# 05_-_BMS.net
KiCad netlist of a schematic drawn in Altium Designer
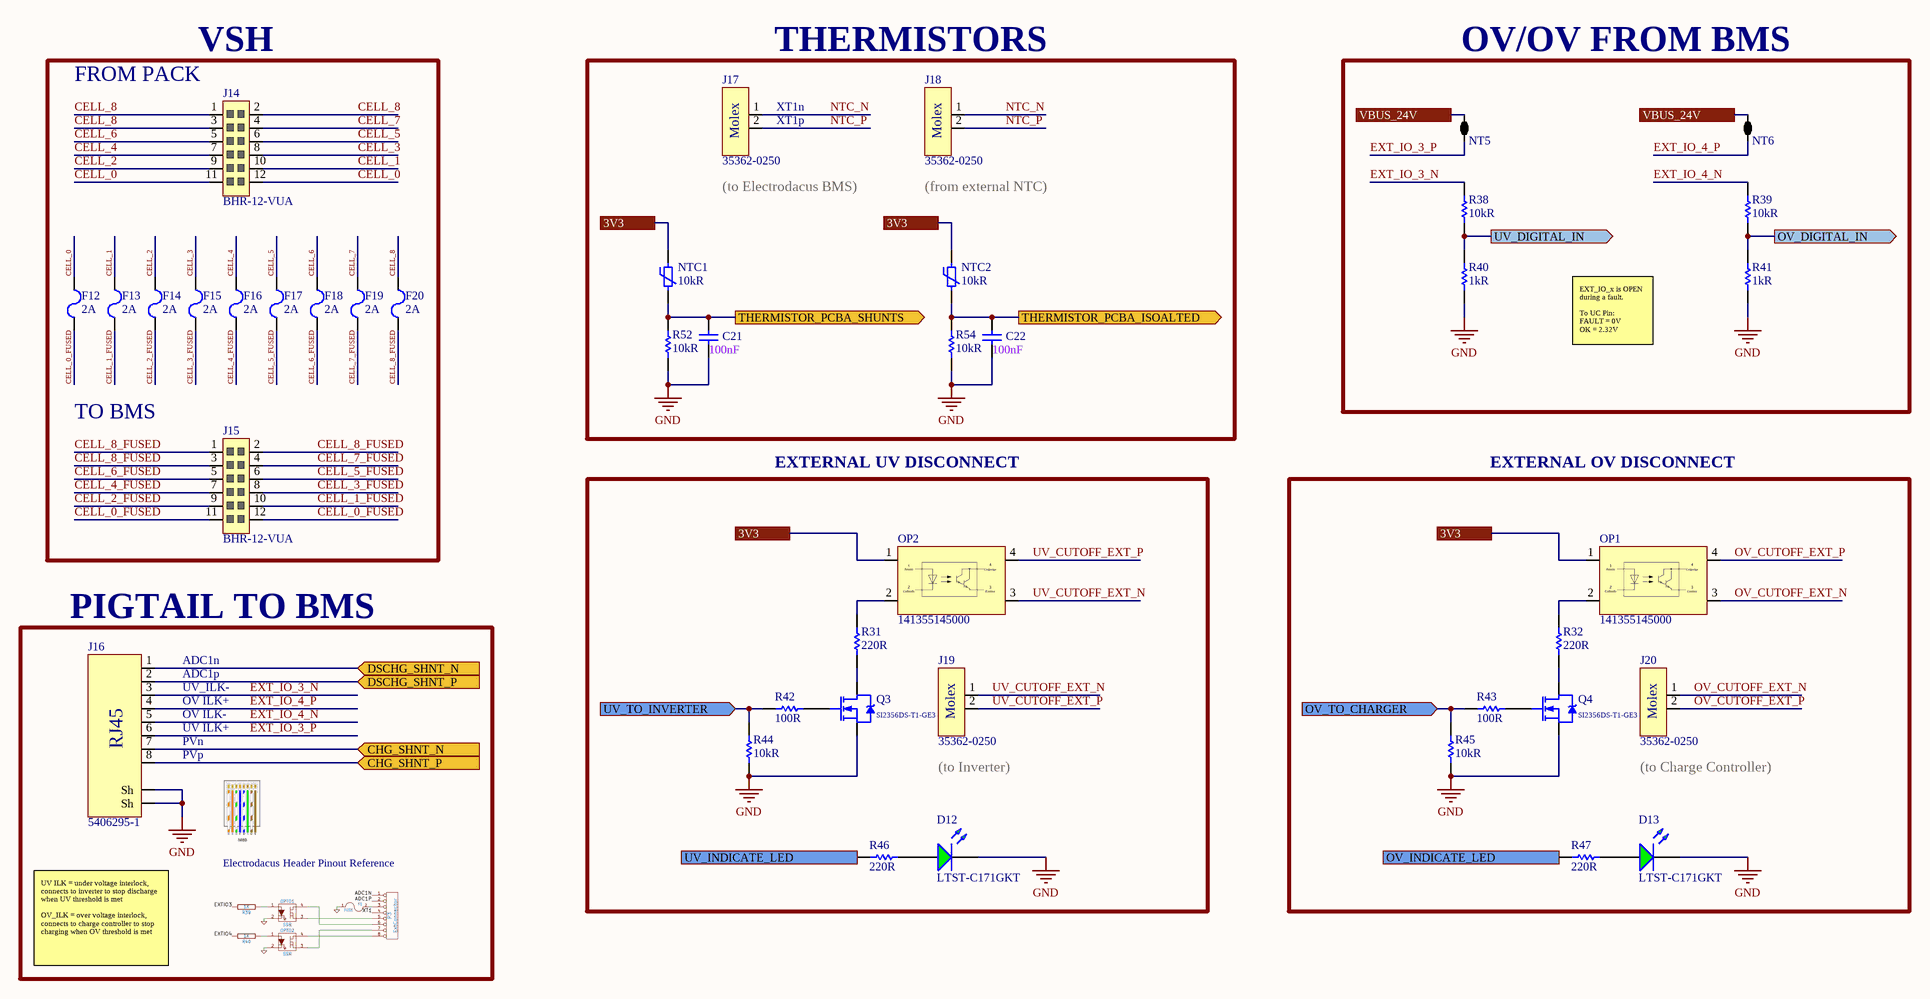
[diagram p0: [05] - BMS.SchDoc]

(export (version "E")
  (design (tool "Eeschema 10.0.6"))
  (components
    (comp (ref "C21")
      (value "100nF")
      (footprint "INCH 0603 - METRIC 1608 - H090")
      (description "CAP CER 0.1UF 25V X7R 0603")
      (fields
        (field (name "MANUFACTURER") "TDK")
        (field (name "MANUFACTURER PART NUMBER") "CGA3E2X7R1E104K080AA")
      )
      (libsource (lib "Capacitors") (part "CGA3E2X7R1E104K080AA"))
    )
    (comp (ref "C22")
      (value "100nF")
      (footprint "INCH 0603 - METRIC 1608 - H090")
      (description "CAP CER 0.1UF 25V X7R 0603")
      (fields
        (field (name "MANUFACTURER") "TDK")
        (field (name "MANUFACTURER PART NUMBER") "CGA3E2X7R1E104K080AA")
      )
      (libsource (lib "Capacitors") (part "CGA3E2X7R1E104K080AA"))
    )
    (comp (ref "D12")
      (value "LTST-C171GKT")
      (footprint "LED - 0805 - GREEN")
      (fields (field (name "MANUFACTURER") "Vishay Lite-On"))
      (libsource (lib "LEDs") (part "LTST-C171GKT"))
    )
    (comp (ref "D13")
      (value "LTST-C171GKT")
      (footprint "LED - 0805 - GREEN")
      (fields (field (name "MANUFACTURER") "Vishay Lite-On"))
      (libsource (lib "LEDs") (part "LTST-C171GKT"))
    )
    (comp (ref "F12")
      (value "MFU0805FF02000P500")
      (footprint "FUSC0805x45")
      (description "FUSE 2A 32V SMT 0805 THIN")
      (fields (field (name "CURRENT RATING") "2A"))
      (libsource (lib "Fuses") (part "MFU0805FF02000P500"))
    )
    (comp (ref "F13")
      (value "MFU0805FF02000P500")
      (footprint "FUSC0805x45")
      (description "FUSE 2A 32V SMT 0805 THIN")
      (fields (field (name "CURRENT RATING") "2A"))
      (libsource (lib "Fuses") (part "MFU0805FF02000P500"))
    )
    (comp (ref "F14")
      (value "MFU0805FF02000P500")
      (footprint "FUSC0805x45")
      (description "FUSE 2A 32V SMT 0805 THIN")
      (fields (field (name "CURRENT RATING") "2A"))
      (libsource (lib "Fuses") (part "MFU0805FF02000P500"))
    )
    (comp (ref "F15")
      (value "MFU0805FF02000P500")
      (footprint "FUSC0805x45")
      (description "FUSE 2A 32V SMT 0805 THIN")
      (fields (field (name "CURRENT RATING") "2A"))
      (libsource (lib "Fuses") (part "MFU0805FF02000P500"))
    )
    (comp (ref "F16")
      (value "MFU0805FF02000P500")
      (footprint "FUSC0805x45")
      (description "FUSE 2A 32V SMT 0805 THIN")
      (fields (field (name "CURRENT RATING") "2A"))
      (libsource (lib "Fuses") (part "MFU0805FF02000P500"))
    )
    (comp (ref "F17")
      (value "MFU0805FF02000P500")
      (footprint "FUSC0805x45")
      (description "FUSE 2A 32V SMT 0805 THIN")
      (fields (field (name "CURRENT RATING") "2A"))
      (libsource (lib "Fuses") (part "MFU0805FF02000P500"))
    )
    (comp (ref "F18")
      (value "MFU0805FF02000P500")
      (footprint "FUSC0805x45")
      (description "FUSE 2A 32V SMT 0805 THIN")
      (fields (field (name "CURRENT RATING") "2A"))
      (libsource (lib "Fuses") (part "MFU0805FF02000P500"))
    )
    (comp (ref "F19")
      (value "MFU0805FF02000P500")
      (footprint "FUSC0805x45")
      (description "FUSE 2A 32V SMT 0805 THIN")
      (fields (field (name "CURRENT RATING") "2A"))
      (libsource (lib "Fuses") (part "MFU0805FF02000P500"))
    )
    (comp (ref "F20")
      (value "MFU0805FF02000P500")
      (footprint "FUSC0805x45")
      (description "FUSE 2A 32V SMT 0805 THIN")
      (fields (field (name "CURRENT RATING") "2A"))
      (libsource (lib "Fuses") (part "MFU0805FF02000P500"))
    )
    (comp (ref "J14")
      (value "BHR-12-VUA")
      (footprint "SHDRV12W64P254_6X2_2284X880H880")
      (description "CONN HEADER VERT 12POS 2.54MM")
      (fields (field (name "MANUFACTURER") "Adam Tech"))
      (libsource (lib "Connectors - Headers") (part "BHR-12-VUA"))
    )
    (comp (ref "J15")
      (value "BHR-12-VUA")
      (footprint "SHDRV12W64P254_6X2_2284X880H880")
      (description "CONN HEADER VERT 12POS 2.54MM")
      (fields (field (name "MANUFACTURER") "Adam Tech"))
      (libsource (lib "Connectors - Headers") (part "BHR-12-VUA"))
    )
    (comp (ref "J16")
      (value "5406295-1")
      (footprint "TE_5406295-1")
      (description "Conn RJ-45 F 8 POS RA Thru-Hole")
      (fields (field (name "MANUFACTURER") "TE Connectivity"))
      (libsource (lib "Connectors") (part "5406295-1"))
    )
    (comp (ref "J17")
      (value "35362-0250")
      (footprint "MOLEX_35362")
      (description "Conn Shrouded Header HDR 2 POS 2mm Solder ST Thru-Hole Bag")
      (fields (field (name "MANUFACTURER") "Molex"))
      (libsource (lib "Connectors") (part "35362-0250"))
    )
    (comp (ref "J18")
      (value "35362-0250")
      (footprint "MOLEX_35362")
      (description "Conn Shrouded Header HDR 2 POS 2mm Solder ST Thru-Hole Bag")
      (fields (field (name "MANUFACTURER") "Molex"))
      (libsource (lib "Connectors") (part "35362-0250"))
    )
    (comp (ref "J19")
      (value "35362-0250")
      (footprint "MOLEX_35362")
      (description "Conn Shrouded Header HDR 2 POS 2mm Solder ST Thru-Hole Bag")
      (fields (field (name "MANUFACTURER") "Molex"))
      (libsource (lib "Connectors") (part "35362-0250"))
    )
    (comp (ref "J20")
      (value "35362-0250")
      (footprint "MOLEX_35362")
      (description "Conn Shrouded Header HDR 2 POS 2mm Solder ST Thru-Hole Bag")
      (fields (field (name "MANUFACTURER") "Molex"))
      (libsource (lib "Connectors") (part "35362-0250"))
    )
    (comp (ref "NT5")
      (value "2 way net tie junction")
      (footprint "2way_LP")
      (libsource (lib "Net Ties") (part "2way"))
    )
    (comp (ref "NT6")
      (value "2 way net tie junction")
      (footprint "2way_LP")
      (libsource (lib "Net Ties") (part "2way"))
    )
    (comp (ref "NTC1")
      (value "10kR")
      (footprint "INCH 0603 - METRIC 1608 - H055N")
      (description "Thermistor NTC 10K Ohm 3% 2-Pin 0603 Surface Mount Solder Pad 3934K T/R")
      (fields
        (field (name "MANUFACTURER") "Murata")
        (field (name "MANUFACTURER PART NUMBER") "NCP18XV103E03RB")
      )
      (libsource (lib "Thermistors") (part "NCP18XV103E03RB"))
    )
    (comp (ref "NTC2")
      (value "10kR")
      (footprint "INCH 0603 - METRIC 1608 - H055N")
      (description "Thermistor NTC 10K Ohm 3% 2-Pin 0603 Surface Mount Solder Pad 3934K T/R")
      (fields
        (field (name "MANUFACTURER") "Murata")
        (field (name "MANUFACTURER PART NUMBER") "NCP18XV103E03RB")
      )
      (libsource (lib "Thermistors") (part "NCP18XV103E03RB"))
    )
    (comp (ref "OP1")
      (value "141355145000")
      (footprint "SOT23-4P127_700X210L50X40N")
      (description "Optocoupler, Transistor, 3.75Kv, Sop Rohs Compliant: Yes")
      (fields (field (name "MANUFACTURER") "Wurth Electronics"))
      (libsource (lib "ICs - Drivers") (part "141355145000"))
    )
    (comp (ref "OP2")
      (value "141355145000")
      (footprint "SOT23-4P127_700X210L50X40N")
      (description "Optocoupler, Transistor, 3.75Kv, Sop Rohs Compliant: Yes")
      (fields (field (name "MANUFACTURER") "Wurth Electronics"))
      (libsource (lib "ICs - Drivers") (part "141355145000"))
    )
    (comp (ref "Q3")
      (value "SI2356DS-T1-GE3")
      (footprint "SOT23-3P95_237X112L50X42N")
      (description "Si2356DS Series 40 V 3.2 A 51 mOhm Surface Mount N-Channel Mosfet - SOT-23-3")
      (fields (field (name "MANUFACTURER") "Vishay Siliconix"))
      (libsource (lib "Transistors - FET") (part "SI2356DS-T1-GE3"))
    )
    (comp (ref "Q4")
      (value "SI2356DS-T1-GE3")
      (footprint "SOT23-3P95_237X112L50X42N")
      (description "Si2356DS Series 40 V 3.2 A 51 mOhm Surface Mount N-Channel Mosfet - SOT-23-3")
      (fields (field (name "MANUFACTURER") "Vishay Siliconix"))
      (libsource (lib "Transistors - FET") (part "SI2356DS-T1-GE3"))
    )
    (comp (ref "R31")
      (value "220R")
      (footprint "INCH 0603 - METRIC 1608 - H055")
      (description "RES SMD 220 OHM 1% 1/10W 0603")
      (fields
        (field (name "MANUFACTURER") "Yageo")
        (field (name "MANUFACTURER PART NUMBER") "RC0603FR-07220RL")
      )
      (libsource (lib "Resistors") (part "RC0603FR-07220RL"))
    )
    (comp (ref "R32")
      (value "220R")
      (footprint "INCH 0603 - METRIC 1608 - H055")
      (description "RES SMD 220 OHM 1% 1/10W 0603")
      (fields
        (field (name "MANUFACTURER") "Yageo")
        (field (name "MANUFACTURER PART NUMBER") "RC0603FR-07220RL")
      )
      (libsource (lib "Resistors") (part "RC0603FR-07220RL"))
    )
    (comp (ref "R38")
      (value "10kR")
      (footprint "INCH 0603 - METRIC 1508 - H050")
      (description "RES SMD 10K OHM 0.5% 1/16W 0603")
      (fields
        (field (name "MANUFACTURER") "Susumu")
        (field (name "MANUFACTURER PART NUMBER") "RR0816P-103-D")
      )
      (libsource (lib "Resistors") (part "RR0816P-103-D"))
    )
    (comp (ref "R39")
      (value "10kR")
      (footprint "INCH 0603 - METRIC 1508 - H050")
      (description "RES SMD 10K OHM 0.5% 1/16W 0603")
      (fields
        (field (name "MANUFACTURER") "Susumu")
        (field (name "MANUFACTURER PART NUMBER") "RR0816P-103-D")
      )
      (libsource (lib "Resistors") (part "RR0816P-103-D"))
    )
    (comp (ref "R40")
      (value "1kR")
      (footprint "INCH 0603 - METRIC 1508 - H050")
      (description "RES SMD 1K OHM 1% 1/10W 0603")
      (fields
        (field (name "MANUFACTURER") "Vishay Dale")
        (field (name "MANUFACTURER PART NUMBER") "CRCW06031K00FKEA")
      )
      (libsource (lib "Resistors") (part "CRCW06031K00FKEA"))
    )
    (comp (ref "R41")
      (value "1kR")
      (footprint "INCH 0603 - METRIC 1508 - H050")
      (description "RES SMD 1K OHM 1% 1/10W 0603")
      (fields
        (field (name "MANUFACTURER") "Vishay Dale")
        (field (name "MANUFACTURER PART NUMBER") "CRCW06031K00FKEA")
      )
      (libsource (lib "Resistors") (part "CRCW06031K00FKEA"))
    )
    (comp (ref "R42")
      (value "100R")
      (footprint "INCH 0603 - METRIC 1608 - H055")
      (description "RES SMD 100 OHM 0.1% 1/16W 0603")
      (fields
        (field (name "MANUFACTURER") "TE Connectivity Neohm")
        (field (name "MANUFACTURER PART NUMBER") "CPF0603B100RE1")
      )
      (libsource (lib "Resistors") (part "CPF0603B100RE1"))
    )
    (comp (ref "R43")
      (value "100R")
      (footprint "INCH 0603 - METRIC 1608 - H055")
      (description "RES SMD 100 OHM 0.1% 1/16W 0603")
      (fields
        (field (name "MANUFACTURER") "TE Connectivity Neohm")
        (field (name "MANUFACTURER PART NUMBER") "CPF0603B100RE1")
      )
      (libsource (lib "Resistors") (part "CPF0603B100RE1"))
    )
    (comp (ref "R44")
      (value "10kR")
      (footprint "INCH 0603 - METRIC 1508 - H050")
      (description "RES SMD 10K OHM 0.5% 1/16W 0603")
      (fields
        (field (name "MANUFACTURER") "Susumu")
        (field (name "MANUFACTURER PART NUMBER") "RR0816P-103-D")
      )
      (libsource (lib "Resistors") (part "RR0816P-103-D"))
    )
    (comp (ref "R45")
      (value "10kR")
      (footprint "INCH 0603 - METRIC 1508 - H050")
      (description "RES SMD 10K OHM 0.5% 1/16W 0603")
      (fields
        (field (name "MANUFACTURER") "Susumu")
        (field (name "MANUFACTURER PART NUMBER") "RR0816P-103-D")
      )
      (libsource (lib "Resistors") (part "RR0816P-103-D"))
    )
    (comp (ref "R46")
      (value "220R")
      (footprint "INCH 0603 - METRIC 1608 - H055")
      (description "RES SMD 220 OHM 1% 1/10W 0603")
      (fields
        (field (name "MANUFACTURER") "Yageo")
        (field (name "MANUFACTURER PART NUMBER") "RC0603FR-07220RL")
      )
      (libsource (lib "Resistors") (part "RC0603FR-07220RL"))
    )
    (comp (ref "R47")
      (value "220R")
      (footprint "INCH 0603 - METRIC 1608 - H055")
      (description "RES SMD 220 OHM 1% 1/10W 0603")
      (fields
        (field (name "MANUFACTURER") "Yageo")
        (field (name "MANUFACTURER PART NUMBER") "RC0603FR-07220RL")
      )
      (libsource (lib "Resistors") (part "RC0603FR-07220RL"))
    )
    (comp (ref "R52")
      (value "10kR")
      (footprint "INCH 0603 - METRIC 1508 - H050")
      (description "RES SMD 10K OHM 0.5% 1/16W 0603")
      (fields
        (field (name "MANUFACTURER") "Susumu")
        (field (name "MANUFACTURER PART NUMBER") "RR0816P-103-D")
      )
      (libsource (lib "Resistors") (part "RR0816P-103-D"))
    )
    (comp (ref "R54")
      (value "10kR")
      (footprint "INCH 0603 - METRIC 1508 - H050")
      (description "RES SMD 10K OHM 0.5% 1/16W 0603")
      (fields
        (field (name "MANUFACTURER") "Susumu")
        (field (name "MANUFACTURER PART NUMBER") "RR0816P-103-D")
      )
      (libsource (lib "Resistors") (part "RR0816P-103-D"))
    )
  )
  (nets
    (net (code "1") (name "/3V3") (class "Default")
      (node (ref "NTC1") (pin "2") (pintype "passive"))
      (node (ref "NTC2") (pin "2") (pintype "passive"))
      (node (ref "OP1") (pin "1") (pinfunction "A_1") (pintype "passive"))
      (node (ref "OP2") (pin "1") (pinfunction "A_1") (pintype "passive"))
    )
    (net (code "2") (name "/CELL_0") (class "Default")
      (node (ref "F12") (pin "1") (pinfunction "1_1") (pintype "passive"))
      (node (ref "J14") (pin "11") (pintype "passive"))
      (node (ref "J14") (pin "12") (pintype "passive"))
    )
    (net (code "3") (name "/CELL_0_FUSED") (class "Default")
      (node (ref "F12") (pin "2") (pinfunction "2_2") (pintype "passive"))
      (node (ref "J15") (pin "11") (pintype "passive"))
      (node (ref "J15") (pin "12") (pintype "passive"))
    )
    (net (code "4") (name "/CELL_1") (class "Default")
      (node (ref "F13") (pin "1") (pinfunction "1_1") (pintype "passive"))
      (node (ref "J14") (pin "10") (pintype "passive"))
    )
    (net (code "5") (name "/CELL_1_FUSED") (class "Default")
      (node (ref "F13") (pin "2") (pinfunction "2_2") (pintype "passive"))
      (node (ref "J15") (pin "10") (pintype "passive"))
    )
    (net (code "6") (name "/CELL_2") (class "Default")
      (node (ref "F14") (pin "1") (pinfunction "1_1") (pintype "passive"))
      (node (ref "J14") (pin "9") (pintype "passive"))
    )
    (net (code "7") (name "/CELL_2_FUSED") (class "Default")
      (node (ref "F14") (pin "2") (pinfunction "2_2") (pintype "passive"))
      (node (ref "J15") (pin "9") (pintype "passive"))
    )
    (net (code "8") (name "/CELL_3") (class "Default")
      (node (ref "F15") (pin "1") (pinfunction "1_1") (pintype "passive"))
      (node (ref "J14") (pin "8") (pintype "passive"))
    )
    (net (code "9") (name "/CELL_3_FUSED") (class "Default")
      (node (ref "F15") (pin "2") (pinfunction "2_2") (pintype "passive"))
      (node (ref "J15") (pin "8") (pintype "passive"))
    )
    (net (code "10") (name "/CELL_4") (class "Default")
      (node (ref "F16") (pin "1") (pinfunction "1_1") (pintype "passive"))
      (node (ref "J14") (pin "7") (pintype "passive"))
    )
    (net (code "11") (name "/CELL_4_FUSED") (class "Default")
      (node (ref "F16") (pin "2") (pinfunction "2_2") (pintype "passive"))
      (node (ref "J15") (pin "7") (pintype "passive"))
    )
    (net (code "12") (name "/CELL_5") (class "Default")
      (node (ref "F17") (pin "1") (pinfunction "1_1") (pintype "passive"))
      (node (ref "J14") (pin "6") (pintype "passive"))
    )
    (net (code "13") (name "/CELL_5_FUSED") (class "Default")
      (node (ref "F17") (pin "2") (pinfunction "2_2") (pintype "passive"))
      (node (ref "J15") (pin "6") (pintype "passive"))
    )
    (net (code "14") (name "/CELL_6") (class "Default")
      (node (ref "F18") (pin "1") (pinfunction "1_1") (pintype "passive"))
      (node (ref "J14") (pin "5") (pintype "passive"))
    )
    (net (code "15") (name "/CELL_6_FUSED") (class "Default")
      (node (ref "F18") (pin "2") (pinfunction "2_2") (pintype "passive"))
      (node (ref "J15") (pin "5") (pintype "passive"))
    )
    (net (code "16") (name "/CELL_7") (class "Default")
      (node (ref "F19") (pin "1") (pinfunction "1_1") (pintype "passive"))
      (node (ref "J14") (pin "4") (pintype "passive"))
    )
    (net (code "17") (name "/CELL_7_FUSED") (class "Default")
      (node (ref "F19") (pin "2") (pinfunction "2_2") (pintype "passive"))
      (node (ref "J15") (pin "4") (pintype "passive"))
    )
    (net (code "18") (name "/CELL_8") (class "Default")
      (node (ref "F20") (pin "1") (pinfunction "1_1") (pintype "passive"))
      (node (ref "J14") (pin "1") (pintype "passive"))
      (node (ref "J14") (pin "2") (pintype "passive"))
      (node (ref "J14") (pin "3") (pintype "passive"))
    )
    (net (code "19") (name "/CELL_8_FUSED") (class "Default")
      (node (ref "F20") (pin "2") (pinfunction "2_2") (pintype "passive"))
      (node (ref "J15") (pin "1") (pintype "passive"))
      (node (ref "J15") (pin "2") (pintype "passive"))
      (node (ref "J15") (pin "3") (pintype "passive"))
    )
    (net (code "20") (name "/CHG_SHNT_N") (class "Default") (node (ref "J16") (pin "7") (pintype "passive")))
    (net (code "21") (name "/CHG_SHNT_P") (class "Default") (node (ref "J16") (pin "8") (pintype "passive")))
    (net (code "22") (name "/DSCHG_SHNT_N") (class "Default")
      (node (ref "J16") (pin "1") (pintype "passive"))
    )
    (net (code "23") (name "/DSCHG_SHNT_P") (class "Default")
      (node (ref "J16") (pin "2") (pintype "passive"))
    )
    (net (code "24") (name "/EXT_IO_3_N") (class "Default")
      (node (ref "J16") (pin "3") (pintype "passive"))
      (node (ref "R38") (pin "2") (pintype "passive"))
    )
    (net (code "25") (name "/EXT_IO_3_P") (class "Default")
      (node (ref "J16") (pin "6") (pintype "passive"))
      (node (ref "NT5") (pin "1") (pinfunction "1_1") (pintype "passive"))
    )
    (net (code "26") (name "/EXT_IO_4_N") (class "Default")
      (node (ref "J16") (pin "5") (pintype "passive"))
      (node (ref "R39") (pin "2") (pintype "passive"))
    )
    (net (code "27") (name "/EXT_IO_4_P") (class "Default")
      (node (ref "J16") (pin "4") (pintype "passive"))
      (node (ref "NT6") (pin "1") (pinfunction "1_1") (pintype "passive"))
    )
    (net (code "28") (name "/NTC_N") (class "Default")
      (node (ref "J17") (pin "1") (pintype "passive"))
      (node (ref "J18") (pin "1") (pintype "passive"))
    )
    (net (code "29") (name "/NTC_P") (class "Default")
      (node (ref "J17") (pin "2") (pintype "passive"))
      (node (ref "J18") (pin "2") (pintype "passive"))
    )
    (net (code "30") (name "/OV_CUTOFF_EXT_N") (class "Default")
      (node (ref "J20") (pin "1") (pintype "passive"))
      (node (ref "OP1") (pin "3") (pinfunction "E_3") (pintype "passive"))
    )
    (net (code "31") (name "/OV_CUTOFF_EXT_P") (class "Default")
      (node (ref "J20") (pin "2") (pintype "passive"))
      (node (ref "OP1") (pin "4") (pinfunction "C_4") (pintype "passive"))
    )
    (net (code "32") (name "/OV_DIGITAL_IN") (class "Default")
      (node (ref "R39") (pin "1") (pintype "passive"))
      (node (ref "R41") (pin "2") (pintype "passive"))
    )
    (net (code "33") (name "/OV_INDICATE_LED") (class "Default")
      (node (ref "R47") (pin "1") (pintype "passive"))
    )
    (net (code "34") (name "/OV_TO_CHARGER") (class "Default")
      (node (ref "R43") (pin "1") (pintype "passive"))
      (node (ref "R45") (pin "2") (pintype "passive"))
    )
    (net (code "35") (name "/THERMISTOR_PCBA_ISOALTED") (class "Default")
      (node (ref "C22") (pin "2") (pintype "passive"))
      (node (ref "NTC2") (pin "1") (pintype "passive"))
      (node (ref "R54") (pin "2") (pintype "passive"))
    )
    (net (code "36") (name "/THERMISTOR_PCBA_SHUNTS") (class "Default")
      (node (ref "C21") (pin "2") (pintype "passive"))
      (node (ref "NTC1") (pin "1") (pintype "passive"))
      (node (ref "R52") (pin "2") (pintype "passive"))
    )
    (net (code "37") (name "/UV_CUTOFF_EXT_N") (class "Default")
      (node (ref "J19") (pin "1") (pintype "passive"))
      (node (ref "OP2") (pin "3") (pinfunction "E_3") (pintype "passive"))
    )
    (net (code "38") (name "/UV_CUTOFF_EXT_P") (class "Default")
      (node (ref "J19") (pin "2") (pintype "passive"))
      (node (ref "OP2") (pin "4") (pinfunction "C_4") (pintype "passive"))
    )
    (net (code "39") (name "/UV_DIGITAL_IN") (class "Default")
      (node (ref "R38") (pin "1") (pintype "passive"))
      (node (ref "R40") (pin "2") (pintype "passive"))
    )
    (net (code "40") (name "/UV_INDICATE_LED") (class "Default")
      (node (ref "R46") (pin "1") (pintype "passive"))
    )
    (net (code "41") (name "/UV_TO_INVERTER") (class "Default")
      (node (ref "R42") (pin "1") (pintype "passive"))
      (node (ref "R44") (pin "2") (pintype "passive"))
    )
    (net (code "42") (name "/VBUS_24V") (class "Default")
      (node (ref "NT5") (pin "2") (pinfunction "2_2") (pintype "passive"))
      (node (ref "NT6") (pin "2") (pinfunction "2_2") (pintype "passive"))
    )
    (net (code "43") (name "GND") (class "Default")
      (node (ref "C21") (pin "1") (pintype "passive"))
      (node (ref "C22") (pin "1") (pintype "passive"))
      (node (ref "D12") (pin "C") (pintype "passive"))
      (node (ref "D13") (pin "C") (pintype "passive"))
      (node (ref "J16") (pin "0") (pinfunction "Sh_0") (pintype "passive"))
      (node (ref "Q3") (pin "2") (pinfunction "S_2") (pintype "passive"))
      (node (ref "Q4") (pin "2") (pinfunction "S_2") (pintype "passive"))
      (node (ref "R40") (pin "1") (pintype "passive"))
      (node (ref "R41") (pin "1") (pintype "passive"))
      (node (ref "R44") (pin "1") (pintype "passive"))
      (node (ref "R45") (pin "1") (pintype "passive"))
      (node (ref "R52") (pin "1") (pintype "passive"))
      (node (ref "R54") (pin "1") (pintype "passive"))
    )
    (net (code "44") (name "Net-(D12-PadA)") (class "Default")
      (node (ref "D12") (pin "A") (pintype "passive"))
      (node (ref "R46") (pin "2") (pintype "passive"))
    )
    (net (code "45") (name "Net-(D13-PadA)") (class "Default")
      (node (ref "D13") (pin "A") (pintype "passive"))
      (node (ref "R47") (pin "2") (pintype "passive"))
    )
    (net (code "46") (name "Net-(OP1-C-Pad2)") (class "Default")
      (node (ref "OP1") (pin "2") (pinfunction "C_2") (pintype "passive"))
      (node (ref "R32") (pin "2") (pintype "passive"))
    )
    (net (code "47") (name "Net-(OP2-C-Pad2)") (class "Default")
      (node (ref "OP2") (pin "2") (pinfunction "C_2") (pintype "passive"))
      (node (ref "R31") (pin "2") (pintype "passive"))
    )
    (net (code "48") (name "Net-(Q3-D)") (class "Default")
      (node (ref "Q3") (pin "3") (pinfunction "D_3") (pintype "passive"))
      (node (ref "R31") (pin "1") (pintype "passive"))
    )
    (net (code "49") (name "Net-(Q3-G)") (class "Default")
      (node (ref "Q3") (pin "1") (pinfunction "G_1") (pintype "passive"))
      (node (ref "R42") (pin "2") (pintype "passive"))
    )
    (net (code "50") (name "Net-(Q4-D)") (class "Default")
      (node (ref "Q4") (pin "3") (pinfunction "D_3") (pintype "passive"))
      (node (ref "R32") (pin "1") (pintype "passive"))
    )
    (net (code "51") (name "Net-(Q4-G)") (class "Default")
      (node (ref "Q4") (pin "1") (pinfunction "G_1") (pintype "passive"))
      (node (ref "R43") (pin "2") (pintype "passive"))
    )
  )
)
